# SCH_LED_capsensor_board_2023-03-21.net
KiCad netlist of a schematic drawn in EasyEDA
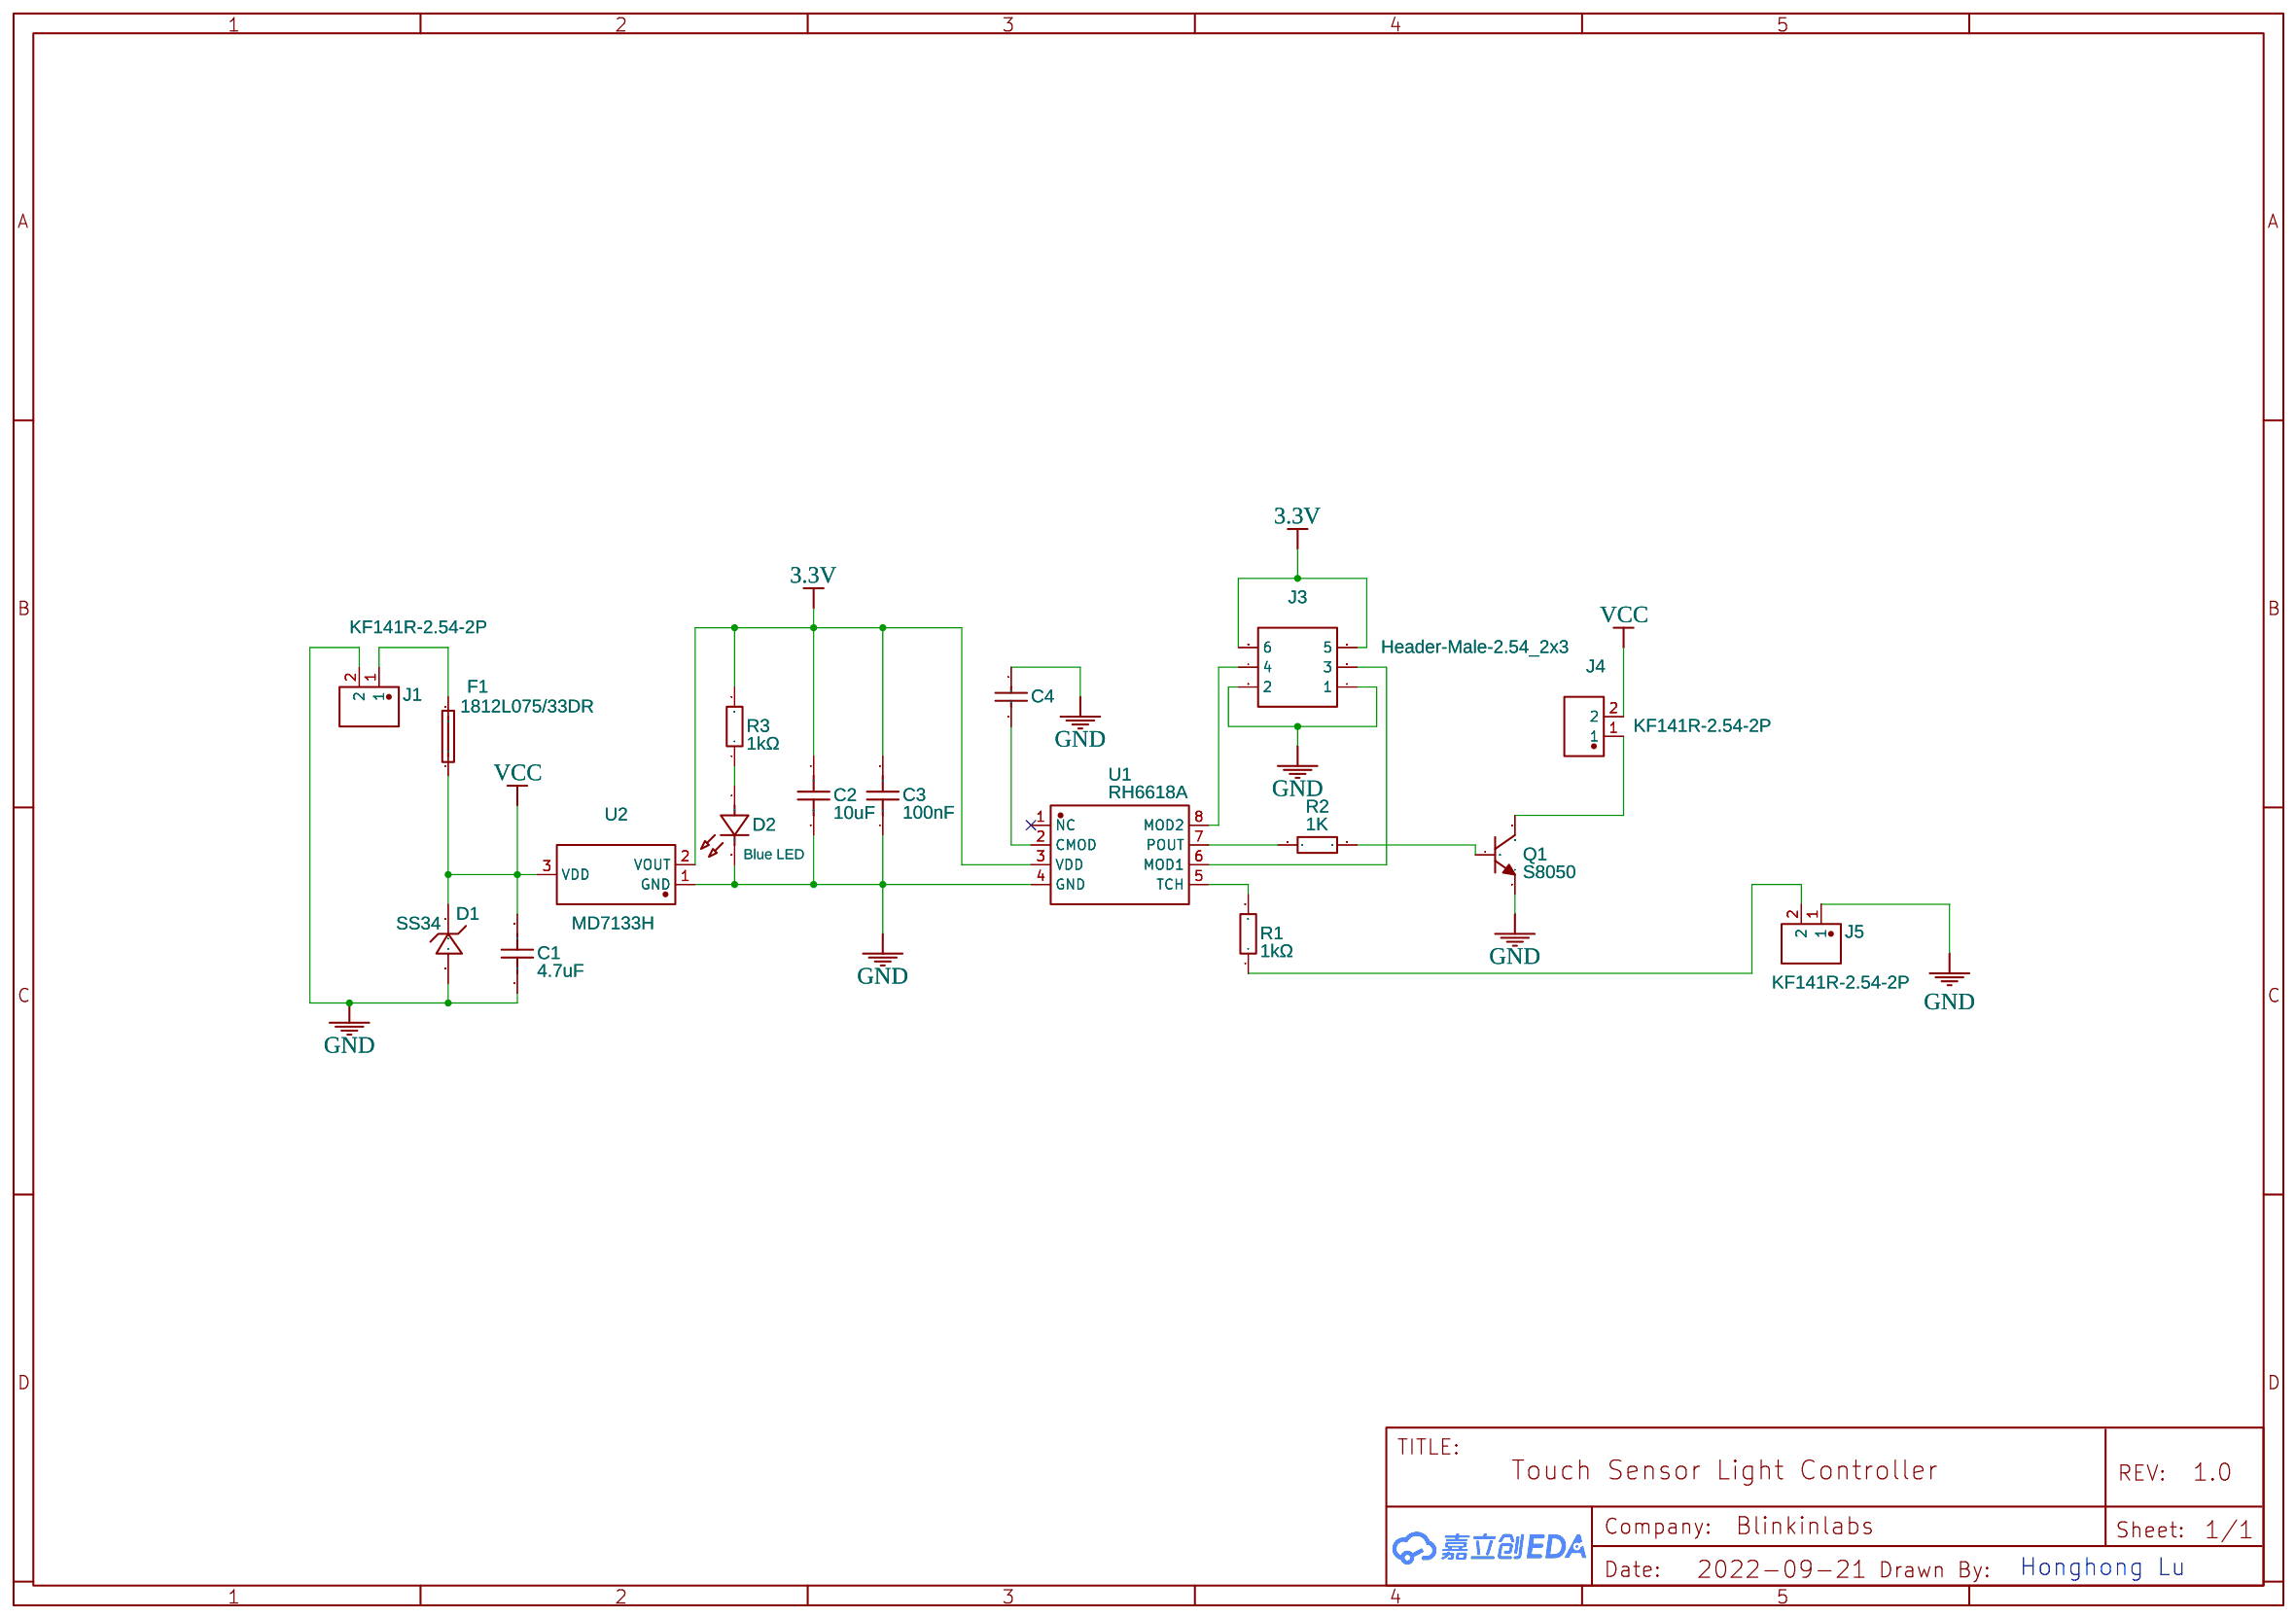
[diagram p0: schematic sheet]

(export (version "E")
  (design (tool "Eeschema 10.0.6"))
  (components
    (comp (ref "C1")
      (value "4.7uF")
      (fields
        (field (name "BOM_Manufacturer Part") "UMK316BJ475KL-T")
        (field (name "BOM_Supplier Part") "C92855")
      )
      (libsource (lib "") (part "TCC1206X7R106K160HT"))
    )
    (comp (ref "C2")
      (value "10uF")
      (fields
        (field (name "BOM_Manufacturer Part") "TCC1206X7R106K160HT")
        (field (name "BOM_Supplier Part") "C380363")
      )
      (libsource (lib "") (part "TCC1206X7R106K160HT_1"))
    )
    (comp (ref "C3")
      (value "100nF")
      (fields
        (field (name "BOM_Manufacturer Part") "CL05B104KB54PNC")
        (field (name "BOM_Supplier Part") "C307331")
      )
      (libsource (lib "") (part "CL05B104KB54PNC"))
    )
    (comp (ref "C4")
      (value "47nF")
      (fields
        (field (name "BOM_Manufacturer Part") "CC0402KRX7R9BB473")
        (field (name "BOM_Supplier Part") "C272875")
      )
      (libsource (lib "") (part "0402CG120J500NT"))
    )
    (comp (ref "D1")
      (value "SS34")
      (fields (field (name "BOM_Supplier Part") "C2923966"))
      (libsource (lib "") (part "SS34A_C2886580"))
    )
    (comp (ref "D2")
      (value "Blue LED")
      (fields
        (field (name "BOM_Manufacturer Part") "16-213/BHC-AN1P2/3T")
        (field (name "BOM_Supplier Part") "C131223")
      )
      (libsource (lib "") (part "XL-1005SURC"))
    )
    (comp (ref "F1")
      (value "1812L075/33DR")
      (fields (field (name "BOM_Supplier Part") "C151170"))
      (libsource (lib "") (part "TLC-MSMD150/20"))
    )
    (comp (ref "J1")
      (value "KF141R-2.54-2P")
      (fields (field (name "BOM_Supplier Part") "C475124"))
      (libsource (lib "") (part "KF141R-2.54-2P_1"))
    )
    (comp (ref "J3")
      (value "Header-Male-2.54_2x3")
      (fields (field (name "BOM_Supplier Part") "C65114"))
      (libsource (lib "") (part "Header-Male-2.54_2x3"))
    )
    (comp (ref "J4")
      (value "KF141R-2.54-2P")
      (fields (field (name "BOM_Supplier Part") "C475124"))
      (libsource (lib "") (part "KF141R-2.54-2P"))
    )
    (comp (ref "J5")
      (value "KF141R-2.54-2P")
      (fields (field (name "BOM_Supplier Part") "C475124"))
      (libsource (lib "") (part "KF141R-2.54-2P_1"))
    )
    (comp (ref "Q1")
      (value "S8050")
      (fields (field (name "BOM_Supplier Part") "C2146"))
      (libsource (lib "") (part "S8050_C2146"))
    )
    (comp (ref "R1")
      (value "1kΩ")
      (fields
        (field (name "BOM_Manufacturer Part") "0402WGF5101TCE")
        (field (name "BOM_Supplier Part") "C25905")
      )
      (libsource (lib "") (part "0402WGF5101TCE_1"))
    )
    (comp (ref "R2")
      (value "1K")
      (fields
        (field (name "BOM_Manufacturer Part") "0402WGF5101TCE")
        (field (name "BOM_Supplier Part") "C25905")
      )
      (libsource (lib "") (part "0402WGF5101TCE"))
    )
    (comp (ref "R3")
      (value "1kΩ")
      (fields
        (field (name "BOM_Manufacturer Part") "0402WGF5101TCE")
        (field (name "BOM_Supplier Part") "C11702")
      )
      (libsource (lib "") (part "0402WGF5101TCE_1"))
    )
    (comp (ref "U1")
      (value "RH6618A")
      (fields (field (name "BOM_Supplier Part") "C511706"))
      (libsource (lib "") (part "RH6618A"))
    )
    (comp (ref "U2")
      (value "MD7133H")
      (fields (field (name "BOM_Supplier Part") "C920377"))
      (libsource (lib "") (part "MD7133H_C920377"))
    )
  )
  (nets
    (net (code "1") (name "3.3V") (class "Default")
      (node (ref "C2") (pin "1") (pinfunction "1_1") (pintype "unspecified"))
      (node (ref "C3") (pin "2") (pinfunction "2_2") (pintype "unspecified"))
      (node (ref "J3") (pin "5") (pinfunction "5_5") (pintype "input"))
      (node (ref "J3") (pin "6") (pinfunction "6_6") (pintype "input"))
      (node (ref "R3") (pin "2") (pinfunction "2_2") (pintype "input"))
      (node (ref "U1") (pin "3") (pinfunction "VDD_3") (pintype "unspecified"))
      (node (ref "U2") (pin "2") (pinfunction "VOUT_2") (pintype "unspecified"))
    )
    (net (code "2") (name "GND") (class "Default")
      (node (ref "C1") (pin "1") (pinfunction "1_1") (pintype "unspecified"))
      (node (ref "C2") (pin "2") (pinfunction "2_2") (pintype "unspecified"))
      (node (ref "C3") (pin "1") (pinfunction "1_1") (pintype "unspecified"))
      (node (ref "C4") (pin "2") (pinfunction "2_2") (pintype "input"))
      (node (ref "D1") (pin "2") (pinfunction "2_2") (pintype "unspecified"))
      (node (ref "D2") (pin "2") (pinfunction "A_2") (pintype "unspecified"))
      (node (ref "J1") (pin "2") (pinfunction "2_2") (pintype "unspecified"))
      (node (ref "J3") (pin "1") (pinfunction "1_1") (pintype "input"))
      (node (ref "J3") (pin "2") (pinfunction "2_2") (pintype "input"))
      (node (ref "J5") (pin "1") (pinfunction "1_1") (pintype "unspecified"))
      (node (ref "Q1") (pin "2") (pinfunction "E_2") (pintype "unspecified"))
      (node (ref "U1") (pin "4") (pinfunction "GND_4") (pintype "unspecified"))
      (node (ref "U2") (pin "1") (pinfunction "GND_1") (pintype "unspecified"))
    )
    (net (code "3") (name "Net-(D2-K)") (class "Default")
      (node (ref "D2") (pin "1") (pinfunction "K_1") (pintype "unspecified"))
      (node (ref "R3") (pin "1") (pinfunction "1_1") (pintype "input"))
    )
    (net (code "4") (name "Net-(F1-Pad2)") (class "Default")
      (node (ref "F1") (pin "2") (pinfunction "2_2") (pintype "unspecified"))
      (node (ref "J1") (pin "1") (pinfunction "1_1") (pintype "unspecified"))
    )
    (net (code "5") (name "Net-(J5-Pad2)") (class "Default")
      (node (ref "J5") (pin "2") (pinfunction "2_2") (pintype "unspecified"))
      (node (ref "R1") (pin "1") (pinfunction "1_1") (pintype "input"))
    )
    (net (code "6") (name "Net-(Q1-B)") (class "Default")
      (node (ref "Q1") (pin "1") (pinfunction "B_1") (pintype "unspecified"))
      (node (ref "R2") (pin "1") (pinfunction "1_1") (pintype "input"))
    )
    (net (code "7") (name "Net-(Q1-C)") (class "Default")
      (node (ref "J4") (pin "1") (pinfunction "1_1") (pintype "unspecified"))
      (node (ref "Q1") (pin "3") (pinfunction "C_3") (pintype "unspecified"))
    )
    (net (code "8") (name "Net-(U1-CMOD)") (class "Default")
      (node (ref "C4") (pin "1") (pinfunction "1_1") (pintype "input"))
      (node (ref "U1") (pin "2") (pinfunction "CMOD_2") (pintype "unspecified"))
    )
    (net (code "9") (name "Net-(U1-MOD1)") (class "Default")
      (node (ref "J3") (pin "3") (pinfunction "3_3") (pintype "input"))
      (node (ref "U1") (pin "6") (pinfunction "MOD1_6") (pintype "unspecified"))
    )
    (net (code "10") (name "Net-(U1-MOD2)") (class "Default")
      (node (ref "J3") (pin "4") (pinfunction "4_4") (pintype "input"))
      (node (ref "U1") (pin "8") (pinfunction "MOD2_8") (pintype "unspecified"))
    )
    (net (code "11") (name "Net-(U1-POUT)") (class "Default")
      (node (ref "R2") (pin "2") (pinfunction "2_2") (pintype "input"))
      (node (ref "U1") (pin "7") (pinfunction "POUT_7") (pintype "unspecified"))
    )
    (net (code "12") (name "Net-(U1-TCH)") (class "Default")
      (node (ref "R1") (pin "2") (pinfunction "2_2") (pintype "input"))
      (node (ref "U1") (pin "5") (pinfunction "TCH_5") (pintype "unspecified"))
    )
    (net (code "13") (name "VCC") (class "Default")
      (node (ref "C1") (pin "2") (pinfunction "2_2") (pintype "unspecified"))
      (node (ref "D1") (pin "1") (pinfunction "1_1") (pintype "unspecified"))
      (node (ref "F1") (pin "1") (pinfunction "1_1") (pintype "unspecified"))
      (node (ref "J4") (pin "2") (pinfunction "2_2") (pintype "unspecified"))
      (node (ref "U2") (pin "3") (pinfunction "VDD_3") (pintype "unspecified"))
    )
    (net (code "14") (name "unconnected-(U1-NC-Pad1)") (class "Default")
      (node (ref "U1") (pin "1") (pinfunction "NC_1") (pintype "unspecified+no_connect"))
    )
  )
)
